# v2164_quad_VC_mixer_w_ext_in_0402.net
KiCad netlist of a schematic drawn in EAGLE
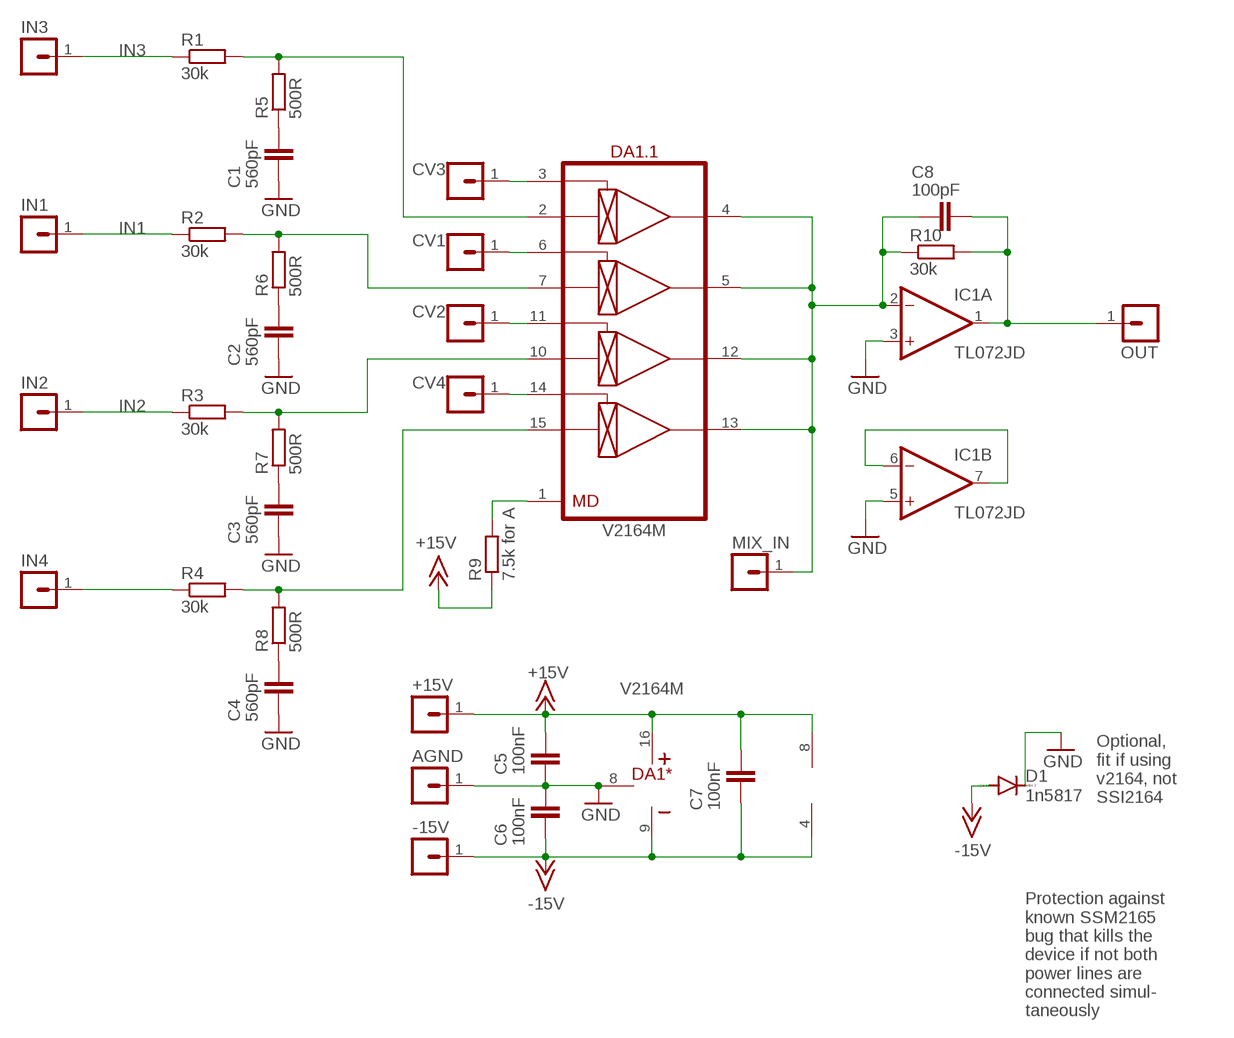
[diagram p0: schematic, sheet 1]

(export (version "E")
  (design (tool "Eeschema 10.0.6"))
  (components
    (comp (ref "+15V")
      (value "MA01-1JN")
      (footprint "eagle-import:MA01N-1J")
      (libsource (lib "eagle-import") (part "MA01-1JN"))
    )
    (comp (ref "-15V")
      (value "MA01-1JN")
      (footprint "eagle-import:MA01N-1J")
      (libsource (lib "eagle-import") (part "MA01-1JN"))
    )
    (comp (ref "AGND")
      (value "MA01-1JN")
      (footprint "eagle-import:MA01N-1J")
      (libsource (lib "eagle-import") (part "MA01-1JN"))
    )
    (comp (ref "C1")
      (value "560pF")
      (footprint "eagle-import:C0603")
      (libsource (lib "eagle-import") (part "C-EUC0603"))
    )
    (comp (ref "C2")
      (value "560pF")
      (footprint "eagle-import:C0603")
      (libsource (lib "eagle-import") (part "C-EUC0603"))
    )
    (comp (ref "C3")
      (value "560pF")
      (footprint "eagle-import:C0603")
      (libsource (lib "eagle-import") (part "C-EUC0603"))
    )
    (comp (ref "C4")
      (value "560pF")
      (footprint "eagle-import:C0603")
      (libsource (lib "eagle-import") (part "C-EUC0603"))
    )
    (comp (ref "C5")
      (value "100nF")
      (footprint "eagle-import:C0402")
      (libsource (lib "eagle-import") (part "C-EUC0402"))
    )
    (comp (ref "C6")
      (value "100nF")
      (footprint "eagle-import:C0402")
      (libsource (lib "eagle-import") (part "C-EUC0402"))
    )
    (comp (ref "C7")
      (value "100nF")
      (footprint "eagle-import:C0402")
      (libsource (lib "eagle-import") (part "C-EUC0402"))
    )
    (comp (ref "C8")
      (value "100pF")
      (footprint "eagle-import:C0402")
      (libsource (lib "eagle-import") (part "C-EUC0402"))
    )
    (comp (ref "CV1")
      (value "MA01-1JN")
      (footprint "eagle-import:MA01N-1J")
      (libsource (lib "eagle-import") (part "MA01-1JN"))
    )
    (comp (ref "CV2")
      (value "MA01-1JN")
      (footprint "eagle-import:MA01N-1J")
      (libsource (lib "eagle-import") (part "MA01-1JN"))
    )
    (comp (ref "CV3")
      (value "MA01-1JN")
      (footprint "eagle-import:MA01N-1J")
      (libsource (lib "eagle-import") (part "MA01-1JN"))
    )
    (comp (ref "CV4")
      (value "MA01-1JN")
      (footprint "eagle-import:MA01N-1J")
      (libsource (lib "eagle-import") (part "MA01-1JN"))
    )
    (comp (ref "D1")
      (value "1n5817")
      (footprint "eagle-import:SOD323-R")
      (libsource (lib "eagle-import") (part "DIODE-SOD323-R"))
    )
    (comp (ref "DA1")
      (value "V2164M")
      (footprint "eagle-import:SO-16")
      (libsource (lib "eagle-import") (part "V2164M"))
    )
    (comp (ref "IC1")
      (value "TL072JD")
      (footprint "eagle-import:SO08J")
      (libsource (lib "eagle-import") (part "TL072JD"))
    )
    (comp (ref "IN1")
      (value "MA01-1JN")
      (footprint "eagle-import:MA01N-1J")
      (libsource (lib "eagle-import") (part "MA01-1JN"))
    )
    (comp (ref "IN2")
      (value "MA01-1JN")
      (footprint "eagle-import:MA01N-1J")
      (libsource (lib "eagle-import") (part "MA01-1JN"))
    )
    (comp (ref "IN3")
      (value "MA01-1JN")
      (footprint "eagle-import:MA01N-1J")
      (libsource (lib "eagle-import") (part "MA01-1JN"))
    )
    (comp (ref "IN4")
      (value "MA01-1JN")
      (footprint "eagle-import:MA01N-1J")
      (libsource (lib "eagle-import") (part "MA01-1JN"))
    )
    (comp (ref "MIX_IN")
      (value "MA01-1JN")
      (footprint "eagle-import:MA01N-1J")
      (libsource (lib "eagle-import") (part "MA01-1JN"))
    )
    (comp (ref "OUT")
      (value "MA01-1JN")
      (footprint "eagle-import:MA01N-1J")
      (libsource (lib "eagle-import") (part "MA01-1JN"))
    )
    (comp (ref "R1")
      (value "30k")
      (footprint "eagle-import:R0402")
      (libsource (lib "eagle-import") (part "R-EU_R0402"))
    )
    (comp (ref "R2")
      (value "30k")
      (footprint "eagle-import:R0402")
      (libsource (lib "eagle-import") (part "R-EU_R0402"))
    )
    (comp (ref "R3")
      (value "30k")
      (footprint "eagle-import:R0402")
      (libsource (lib "eagle-import") (part "R-EU_R0402"))
    )
    (comp (ref "R4")
      (value "30k")
      (footprint "eagle-import:R0402")
      (libsource (lib "eagle-import") (part "R-EU_R0402"))
    )
    (comp (ref "R5")
      (value "500R")
      (footprint "eagle-import:R0402")
      (libsource (lib "eagle-import") (part "R-EU_R0402"))
    )
    (comp (ref "R6")
      (value "500R")
      (footprint "eagle-import:R0402")
      (libsource (lib "eagle-import") (part "R-EU_R0402"))
    )
    (comp (ref "R7")
      (value "500R")
      (footprint "eagle-import:R0402")
      (libsource (lib "eagle-import") (part "R-EU_R0402"))
    )
    (comp (ref "R8")
      (value "500R")
      (footprint "eagle-import:R0402")
      (libsource (lib "eagle-import") (part "R-EU_R0402"))
    )
    (comp (ref "R9")
      (value "7.5k for A")
      (footprint "eagle-import:R0402")
      (libsource (lib "eagle-import") (part "R-EU_R0402"))
    )
    (comp (ref "R10")
      (value "30k")
      (footprint "eagle-import:R0402")
      (libsource (lib "eagle-import") (part "R-EU_R0402"))
    )
  )
  (nets
    (net (code "1") (name "+15V") (class "Default")
      (node (ref "+15V") (pin "1") (pinfunction "1_1") (pintype "passive"))
      (node (ref "C5") (pin "2") (pinfunction "2_2") (pintype "passive"))
      (node (ref "C7") (pin "2") (pinfunction "2_2") (pintype "passive"))
      (node (ref "DA1") (pin "16") (pinfunction "V+_16") (pintype "power_in"))
      (node (ref "IC1") (pin "8") (pinfunction "V+_8") (pintype "power_in"))
      (node (ref "R9") (pin "1") (pinfunction "1_1") (pintype "passive"))
    )
    (net (code "2") (name "-15V") (class "Default")
      (node (ref "-15V") (pin "1") (pinfunction "1_1") (pintype "passive"))
      (node (ref "C6") (pin "1") (pinfunction "1_1") (pintype "passive"))
      (node (ref "C7") (pin "1") (pinfunction "1_1") (pintype "passive"))
      (node (ref "D1") (pin "A") (pinfunction "A_A") (pintype "passive"))
      (node (ref "DA1") (pin "9") (pinfunction "V-_9") (pintype "power_in"))
      (node (ref "IC1") (pin "4") (pinfunction "V-_4") (pintype "power_in"))
    )
    (net (code "3") (name "/IN1") (class "Default")
      (node (ref "IN1") (pin "1") (pinfunction "1_1") (pintype "passive"))
      (node (ref "R2") (pin "1") (pinfunction "1_1") (pintype "passive"))
    )
    (net (code "4") (name "/IN2") (class "Default")
      (node (ref "IN2") (pin "1") (pinfunction "1_1") (pintype "passive"))
      (node (ref "R3") (pin "1") (pinfunction "1_1") (pintype "passive"))
    )
    (net (code "5") (name "/IN3") (class "Default")
      (node (ref "IN3") (pin "1") (pinfunction "1_1") (pintype "passive"))
      (node (ref "R1") (pin "1") (pinfunction "1_1") (pintype "passive"))
    )
    (net (code "6") (name "GND") (class "Default")
      (node (ref "AGND") (pin "1") (pinfunction "1_1") (pintype "passive"))
      (node (ref "C1") (pin "1") (pinfunction "1_1") (pintype "passive"))
      (node (ref "C2") (pin "1") (pinfunction "1_1") (pintype "passive"))
      (node (ref "C3") (pin "1") (pinfunction "1_1") (pintype "passive"))
      (node (ref "C4") (pin "1") (pinfunction "1_1") (pintype "passive"))
      (node (ref "C5") (pin "1") (pinfunction "1_1") (pintype "passive"))
      (node (ref "C6") (pin "2") (pinfunction "2_2") (pintype "passive"))
      (node (ref "D1") (pin "C") (pinfunction "C_C") (pintype "passive"))
      (node (ref "DA1") (pin "8") (pinfunction "GND_8") (pintype "power_in"))
      (node (ref "IC1") (pin "3") (pinfunction "+IN_3") (pintype "input"))
      (node (ref "IC1") (pin "5") (pinfunction "+IN_5") (pintype "input"))
    )
    (net (code "7") (name "Net-(C1-Pad2)") (class "Default")
      (node (ref "C1") (pin "2") (pinfunction "2_2") (pintype "passive"))
      (node (ref "R5") (pin "1") (pinfunction "1_1") (pintype "passive"))
    )
    (net (code "8") (name "Net-(C2-Pad2)") (class "Default")
      (node (ref "C2") (pin "2") (pinfunction "2_2") (pintype "passive"))
      (node (ref "R6") (pin "1") (pinfunction "1_1") (pintype "passive"))
    )
    (net (code "9") (name "Net-(C3-Pad2)") (class "Default")
      (node (ref "C3") (pin "2") (pinfunction "2_2") (pintype "passive"))
      (node (ref "R7") (pin "1") (pinfunction "1_1") (pintype "passive"))
    )
    (net (code "10") (name "Net-(C4-Pad2)") (class "Default")
      (node (ref "C4") (pin "2") (pinfunction "2_2") (pintype "passive"))
      (node (ref "R8") (pin "1") (pinfunction "1_1") (pintype "passive"))
    )
    (net (code "11") (name "Net-(DA1B-CV1)") (class "Default")
      (node (ref "CV3") (pin "1") (pinfunction "1_1") (pintype "passive"))
      (node (ref "DA1") (pin "3") (pinfunction "CV1_3") (pintype "input"))
    )
    (net (code "12") (name "Net-(DA1B-CV2)") (class "Default")
      (node (ref "CV1") (pin "1") (pinfunction "1_1") (pintype "passive"))
      (node (ref "DA1") (pin "6") (pinfunction "CV2_6") (pintype "input"))
    )
    (net (code "13") (name "Net-(DA1B-CV3)") (class "Default")
      (node (ref "CV2") (pin "1") (pinfunction "1_1") (pintype "passive"))
      (node (ref "DA1") (pin "11") (pinfunction "CV3_11") (pintype "input"))
    )
    (net (code "14") (name "Net-(DA1B-CV4)") (class "Default")
      (node (ref "CV4") (pin "1") (pinfunction "1_1") (pintype "passive"))
      (node (ref "DA1") (pin "14") (pinfunction "CV4_14") (pintype "input"))
    )
    (net (code "15") (name "Net-(DA1B-IN1)") (class "Default")
      (node (ref "DA1") (pin "2") (pinfunction "IN1_2") (pintype "input"))
      (node (ref "R1") (pin "2") (pinfunction "2_2") (pintype "passive"))
      (node (ref "R5") (pin "2") (pinfunction "2_2") (pintype "passive"))
    )
    (net (code "16") (name "Net-(DA1B-IN2)") (class "Default")
      (node (ref "DA1") (pin "7") (pinfunction "IN2_7") (pintype "input"))
      (node (ref "R2") (pin "2") (pinfunction "2_2") (pintype "passive"))
      (node (ref "R6") (pin "2") (pinfunction "2_2") (pintype "passive"))
    )
    (net (code "17") (name "Net-(DA1B-IN3)") (class "Default")
      (node (ref "DA1") (pin "10") (pinfunction "IN3_10") (pintype "input"))
      (node (ref "R3") (pin "2") (pinfunction "2_2") (pintype "passive"))
      (node (ref "R7") (pin "2") (pinfunction "2_2") (pintype "passive"))
    )
    (net (code "18") (name "Net-(DA1B-IN4)") (class "Default")
      (node (ref "DA1") (pin "15") (pinfunction "IN4_15") (pintype "input"))
      (node (ref "R4") (pin "2") (pinfunction "2_2") (pintype "passive"))
      (node (ref "R8") (pin "2") (pinfunction "2_2") (pintype "passive"))
    )
    (net (code "19") (name "Net-(DA1B-MD)") (class "Default")
      (node (ref "DA1") (pin "1") (pinfunction "MD_1") (pintype "output"))
      (node (ref "R9") (pin "2") (pinfunction "2_2") (pintype "passive"))
    )
    (net (code "20") (name "Net-(DA1B-OUT1)") (class "Default")
      (node (ref "C8") (pin "1") (pinfunction "1_1") (pintype "passive"))
      (node (ref "DA1") (pin "12") (pinfunction "OUT3_12") (pintype "output"))
      (node (ref "DA1") (pin "13") (pinfunction "OUT4_13") (pintype "output"))
      (node (ref "DA1") (pin "4") (pinfunction "OUT1_4") (pintype "output"))
      (node (ref "DA1") (pin "5") (pinfunction "OUT2_5") (pintype "output"))
      (node (ref "IC1") (pin "2") (pinfunction "-IN_2") (pintype "input"))
      (node (ref "MIX_IN") (pin "1") (pinfunction "1_1") (pintype "passive"))
      (node (ref "R10") (pin "1") (pinfunction "1_1") (pintype "passive"))
    )
    (net (code "21") (name "Net-(IC1A-OUT)") (class "Default")
      (node (ref "C8") (pin "2") (pinfunction "2_2") (pintype "passive"))
      (node (ref "IC1") (pin "1") (pinfunction "OUT_1") (pintype "output"))
      (node (ref "OUT") (pin "1") (pinfunction "1_1") (pintype "passive"))
      (node (ref "R10") (pin "2") (pinfunction "2_2") (pintype "passive"))
    )
    (net (code "22") (name "Net-(IC1B--IN)") (class "Default")
      (node (ref "IC1") (pin "6") (pinfunction "-IN_6") (pintype "input"))
      (node (ref "IC1") (pin "7") (pinfunction "OUT_7") (pintype "output"))
    )
    (net (code "23") (name "Net-(IN4-Pad1)") (class "Default")
      (node (ref "IN4") (pin "1") (pinfunction "1_1") (pintype "passive"))
      (node (ref "R4") (pin "1") (pinfunction "1_1") (pintype "passive"))
    )
  )
)
